# OLM-periph-probe_ambientREVA.net
KiCad netlist of a schematic drawn in EAGLE
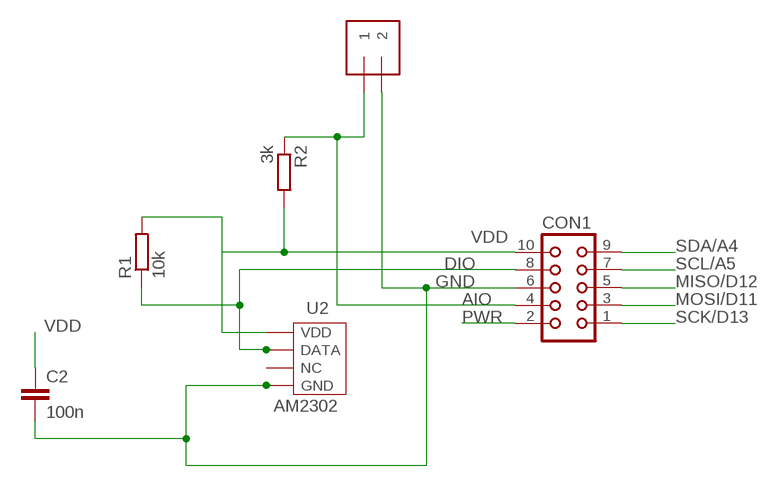
[diagram p0: schematic, sheet 1]

(export (version "E")
  (design (tool "Eeschema 10.0.6"))
  (components
    (comp (ref "C2")
      (value "100n")
      (footprint "eagle-import:C025-024X044")
      (libsource (lib "eagle-import") (part "C-EU025-024X044"))
    )
    (comp (ref "CON1")
      (value "CON10L")
      (footprint "eagle-import:CON10L")
      (libsource (lib "eagle-import") (part "CON10L"))
    )
    (comp (ref "J1")
      (value "1X2-3.5MM")
      (footprint "eagle-import:1X2-3.5MM")
      (libsource (lib "eagle-import") (part "1X2-3.5MM"))
    )
    (comp (ref "R1")
      (value "10k")
      (footprint "eagle-import:0204_7")
      (libsource (lib "eagle-import") (part "R-EU_0204/7"))
    )
    (comp (ref "R2")
      (value "3k")
      (footprint "eagle-import:0204_7")
      (libsource (lib "eagle-import") (part "R-EU_0204/7"))
    )
    (comp (ref "U2")
      (value "AM2302")
      (footprint "eagle-import:AM2302")
      (libsource (lib "eagle-import") (part "AM2302"))
    )
  )
  (nets
    (net (code "1") (name "/AIO") (class "Default")
      (node (ref "CON1") (pin "4") (pinfunction "4_4") (pintype "passive"))
      (node (ref "J1") (pin "1") (pinfunction "1_1") (pintype "passive"))
      (node (ref "R2") (pin "1") (pinfunction "1_1") (pintype "passive"))
    )
    (net (code "2") (name "/DIO") (class "Default")
      (node (ref "CON1") (pin "8") (pinfunction "8_8") (pintype "passive"))
      (node (ref "R1") (pin "1") (pinfunction "1_1") (pintype "passive"))
      (node (ref "U2") (pin "P$2") (pinfunction "DATA_P$2") (pintype "bidirectional"))
    )
    (net (code "3") (name "/GND") (class "Default")
      (node (ref "C2") (pin "2") (pinfunction "2_2") (pintype "passive"))
      (node (ref "CON1") (pin "6") (pinfunction "6_6") (pintype "passive"))
      (node (ref "J1") (pin "2") (pinfunction "2_2") (pintype "passive"))
      (node (ref "U2") (pin "P$4") (pinfunction "GND_P$4") (pintype "power_in"))
    )
    (net (code "4") (name "/MISO{slash}D12") (class "Default")
      (node (ref "CON1") (pin "5") (pinfunction "5_5") (pintype "passive"))
    )
    (net (code "5") (name "/MOSI{slash}D11") (class "Default")
      (node (ref "CON1") (pin "3") (pinfunction "3_3") (pintype "passive"))
    )
    (net (code "6") (name "/PWR") (class "Default")
      (node (ref "CON1") (pin "2") (pinfunction "2_2") (pintype "passive"))
    )
    (net (code "7") (name "/SCK{slash}D13") (class "Default")
      (node (ref "CON1") (pin "1") (pinfunction "1_1") (pintype "passive"))
    )
    (net (code "8") (name "/SCL{slash}A5") (class "Default")
      (node (ref "CON1") (pin "7") (pinfunction "7_7") (pintype "passive"))
    )
    (net (code "9") (name "/SDA{slash}A4") (class "Default")
      (node (ref "CON1") (pin "9") (pinfunction "9_9") (pintype "passive"))
    )
    (net (code "10") (name "/VDD") (class "Default")
      (node (ref "C2") (pin "1") (pinfunction "1_1") (pintype "passive"))
      (node (ref "CON1") (pin "10") (pinfunction "10_10") (pintype "passive"))
      (node (ref "R1") (pin "2") (pinfunction "2_2") (pintype "passive"))
      (node (ref "R2") (pin "2") (pinfunction "2_2") (pintype "passive"))
      (node (ref "U2") (pin "P$1") (pinfunction "VDD_P$1") (pintype "power_in"))
    )
    (net (code "11") (name "unconnected-(U2-NC-PadP$3)") (class "Default")
      (node (ref "U2") (pin "P$3") (pinfunction "NC_P$3") (pintype "no_connect"))
    )
  )
)
